# Audio-Reg.net
KiCad netlist of a schematic drawn in EAGLE
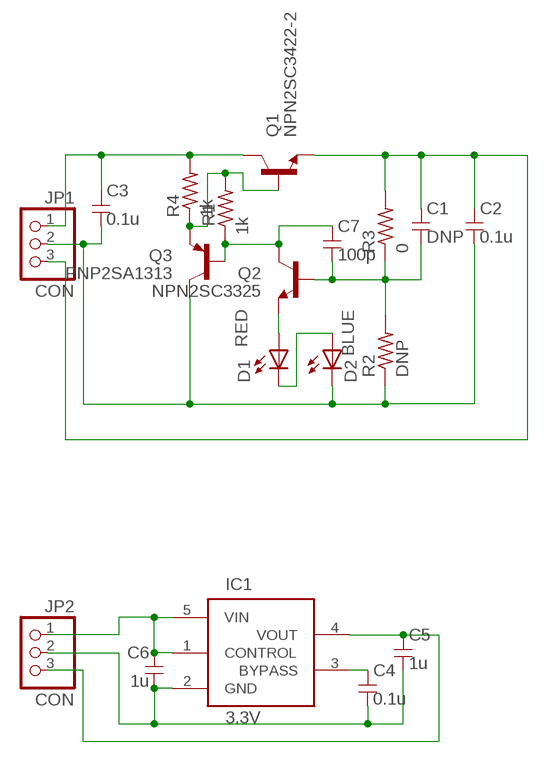
[diagram p0: schematic, sheet 1]

(export (version "E")
  (design (tool "Eeschema 10.0.6"))
  (components
    (comp (ref "C1")
      (value "DNP")
      (footprint "eagle-import:1608")
      (libsource (lib "eagle-import") (part "C-1608"))
    )
    (comp (ref "C2")
      (value "0.1u")
      (footprint "eagle-import:1608")
      (libsource (lib "eagle-import") (part "C-1608"))
    )
    (comp (ref "C3")
      (value "0.1u")
      (footprint "eagle-import:1608")
      (libsource (lib "eagle-import") (part "C-1608"))
    )
    (comp (ref "C4")
      (value "0.1u")
      (footprint "eagle-import:1608")
      (libsource (lib "eagle-import") (part "C-1608"))
    )
    (comp (ref "C5")
      (value "1u")
      (footprint "eagle-import:1608")
      (libsource (lib "eagle-import") (part "C-1608"))
    )
    (comp (ref "C6")
      (value "1u")
      (footprint "eagle-import:1608")
      (libsource (lib "eagle-import") (part "C-1608"))
    )
    (comp (ref "C7")
      (value "100p")
      (footprint "eagle-import:1608")
      (libsource (lib "eagle-import") (part "C-1608"))
    )
    (comp (ref "D1")
      (value "RED")
      (footprint "eagle-import:D1608")
      (libsource (lib "eagle-import") (part "LED-SMD1608"))
    )
    (comp (ref "D2")
      (value "BLUE")
      (footprint "eagle-import:D1608")
      (libsource (lib "eagle-import") (part "LED-SMD1608"))
    )
    (comp (ref "IC1")
      (value "3.3V")
      (footprint "eagle-import:SOT23-5")
      (libsource (lib "eagle-import") (part "NJM2863"))
    )
    (comp (ref "JP1")
      (value "CON")
      (footprint "eagle-import:1X03")
      (libsource (lib "eagle-import") (part "PINHD-1X3"))
    )
    (comp (ref "JP2")
      (value "CON")
      (footprint "eagle-import:1X03")
      (libsource (lib "eagle-import") (part "PINHD-1X3"))
    )
    (comp (ref "Q1")
      (value "NPN2SC3422-2")
      (footprint "eagle-import:TO126-2")
      (libsource (lib "eagle-import") (part "NPN2SC3422-2"))
    )
    (comp (ref "Q2")
      (value "NPN2SC3325")
      (footprint "eagle-import:SC59")
      (libsource (lib "eagle-import") (part "NPN2SC3325"))
    )
    (comp (ref "Q3")
      (value "PNP2SA1313")
      (footprint "eagle-import:SC59")
      (libsource (lib "eagle-import") (part "PNP2SA1313"))
    )
    (comp (ref "R1")
      (value "1k")
      (footprint "eagle-import:1608")
      (libsource (lib "eagle-import") (part "R-1608"))
    )
    (comp (ref "R2")
      (value "DNP")
      (footprint "eagle-import:1608")
      (libsource (lib "eagle-import") (part "R-1608"))
    )
    (comp (ref "R3")
      (value "0")
      (footprint "eagle-import:1608")
      (libsource (lib "eagle-import") (part "R-1608"))
    )
    (comp (ref "R4")
      (value "1k")
      (footprint "eagle-import:1608")
      (libsource (lib "eagle-import") (part "R-1608"))
    )
  )
  (nets
    (net (code "1") (name "Net-(D1-PadK)") (class "Default")
      (node (ref "D1") (pin "K") (pinfunction "K_K") (pintype "passive"))
      (node (ref "D2") (pin "A") (pinfunction "A_A") (pintype "passive"))
    )
    (net (code "2") (name "Net-(IC1-BYPASS)") (class "Default")
      (node (ref "C4") (pin "1") (pinfunction "1_1") (pintype "passive"))
      (node (ref "IC1") (pin "3") (pinfunction "BYPASS_3") (pintype "passive"))
    )
    (net (code "3") (name "Net-(IC1-CONTROL)") (class "Default")
      (node (ref "C6") (pin "1") (pinfunction "1_1") (pintype "passive"))
      (node (ref "IC1") (pin "1") (pinfunction "CONTROL_1") (pintype "input"))
      (node (ref "IC1") (pin "5") (pinfunction "VIN_5") (pintype "power_in"))
      (node (ref "JP2") (pin "1") (pinfunction "1_1") (pintype "passive"))
    )
    (net (code "4") (name "Net-(IC1-GND)") (class "Default")
      (node (ref "C4") (pin "2") (pinfunction "2_2") (pintype "passive"))
      (node (ref "C5") (pin "2") (pinfunction "2_2") (pintype "passive"))
      (node (ref "C6") (pin "2") (pinfunction "2_2") (pintype "passive"))
      (node (ref "IC1") (pin "2") (pinfunction "GND_2") (pintype "power_in"))
      (node (ref "JP2") (pin "2") (pinfunction "2_2") (pintype "passive"))
    )
    (net (code "5") (name "Net-(IC1-VOUT)") (class "Default")
      (node (ref "C5") (pin "1") (pinfunction "1_1") (pintype "passive"))
      (node (ref "IC1") (pin "4") (pinfunction "VOUT_4") (pintype "power_in"))
      (node (ref "JP2") (pin "3") (pinfunction "3_3") (pintype "passive"))
    )
    (net (code "6") (name "Net-(Q1-B)") (class "Default")
      (node (ref "Q1") (pin "3") (pinfunction "B_3") (pintype "passive"))
      (node (ref "Q3") (pin "2") (pinfunction "E_2") (pintype "passive"))
      (node (ref "R1") (pin "2") (pinfunction "2_2") (pintype "passive"))
      (node (ref "R4") (pin "1") (pinfunction "1_1") (pintype "passive"))
    )
    (net (code "7") (name "Net-(Q1-C)") (class "Default")
      (node (ref "C3") (pin "1") (pinfunction "1_1") (pintype "passive"))
      (node (ref "JP1") (pin "1") (pinfunction "1_1") (pintype "passive"))
      (node (ref "Q1") (pin "2") (pinfunction "C_2") (pintype "passive"))
      (node (ref "R4") (pin "2") (pinfunction "2_2") (pintype "passive"))
    )
    (net (code "8") (name "Net-(Q1-E)") (class "Default")
      (node (ref "C1") (pin "1") (pinfunction "1_1") (pintype "passive"))
      (node (ref "C2") (pin "1") (pinfunction "1_1") (pintype "passive"))
      (node (ref "JP1") (pin "3") (pinfunction "3_3") (pintype "passive"))
      (node (ref "Q1") (pin "1") (pinfunction "E_1") (pintype "passive"))
      (node (ref "R3") (pin "2") (pinfunction "2_2") (pintype "passive"))
    )
    (net (code "9") (name "Net-(Q2-B)") (class "Default")
      (node (ref "C1") (pin "2") (pinfunction "2_2") (pintype "passive"))
      (node (ref "C7") (pin "2") (pinfunction "2_2") (pintype "passive"))
      (node (ref "Q2") (pin "1") (pinfunction "B_1") (pintype "passive"))
      (node (ref "R2") (pin "2") (pinfunction "2_2") (pintype "passive"))
      (node (ref "R3") (pin "1") (pinfunction "1_1") (pintype "passive"))
    )
    (net (code "10") (name "Net-(Q2-C)") (class "Default")
      (node (ref "C7") (pin "1") (pinfunction "1_1") (pintype "passive"))
      (node (ref "Q2") (pin "3") (pinfunction "C_3") (pintype "passive"))
      (node (ref "Q3") (pin "1") (pinfunction "B_1") (pintype "passive"))
      (node (ref "R1") (pin "1") (pinfunction "1_1") (pintype "passive"))
    )
    (net (code "11") (name "Net-(Q2-E)") (class "Default")
      (node (ref "D1") (pin "A") (pinfunction "A_A") (pintype "passive"))
      (node (ref "Q2") (pin "2") (pinfunction "E_2") (pintype "passive"))
    )
    (net (code "12") (name "Net-(Q3-C)") (class "Default")
      (node (ref "C2") (pin "2") (pinfunction "2_2") (pintype "passive"))
      (node (ref "C3") (pin "2") (pinfunction "2_2") (pintype "passive"))
      (node (ref "D2") (pin "K") (pinfunction "K_K") (pintype "passive"))
      (node (ref "JP1") (pin "2") (pinfunction "2_2") (pintype "passive"))
      (node (ref "Q3") (pin "3") (pinfunction "C_3") (pintype "passive"))
      (node (ref "R2") (pin "1") (pinfunction "1_1") (pintype "passive"))
    )
  )
)
